# MCU_GPS_Comms.net
KiCad netlist of a schematic drawn in Altium Designer
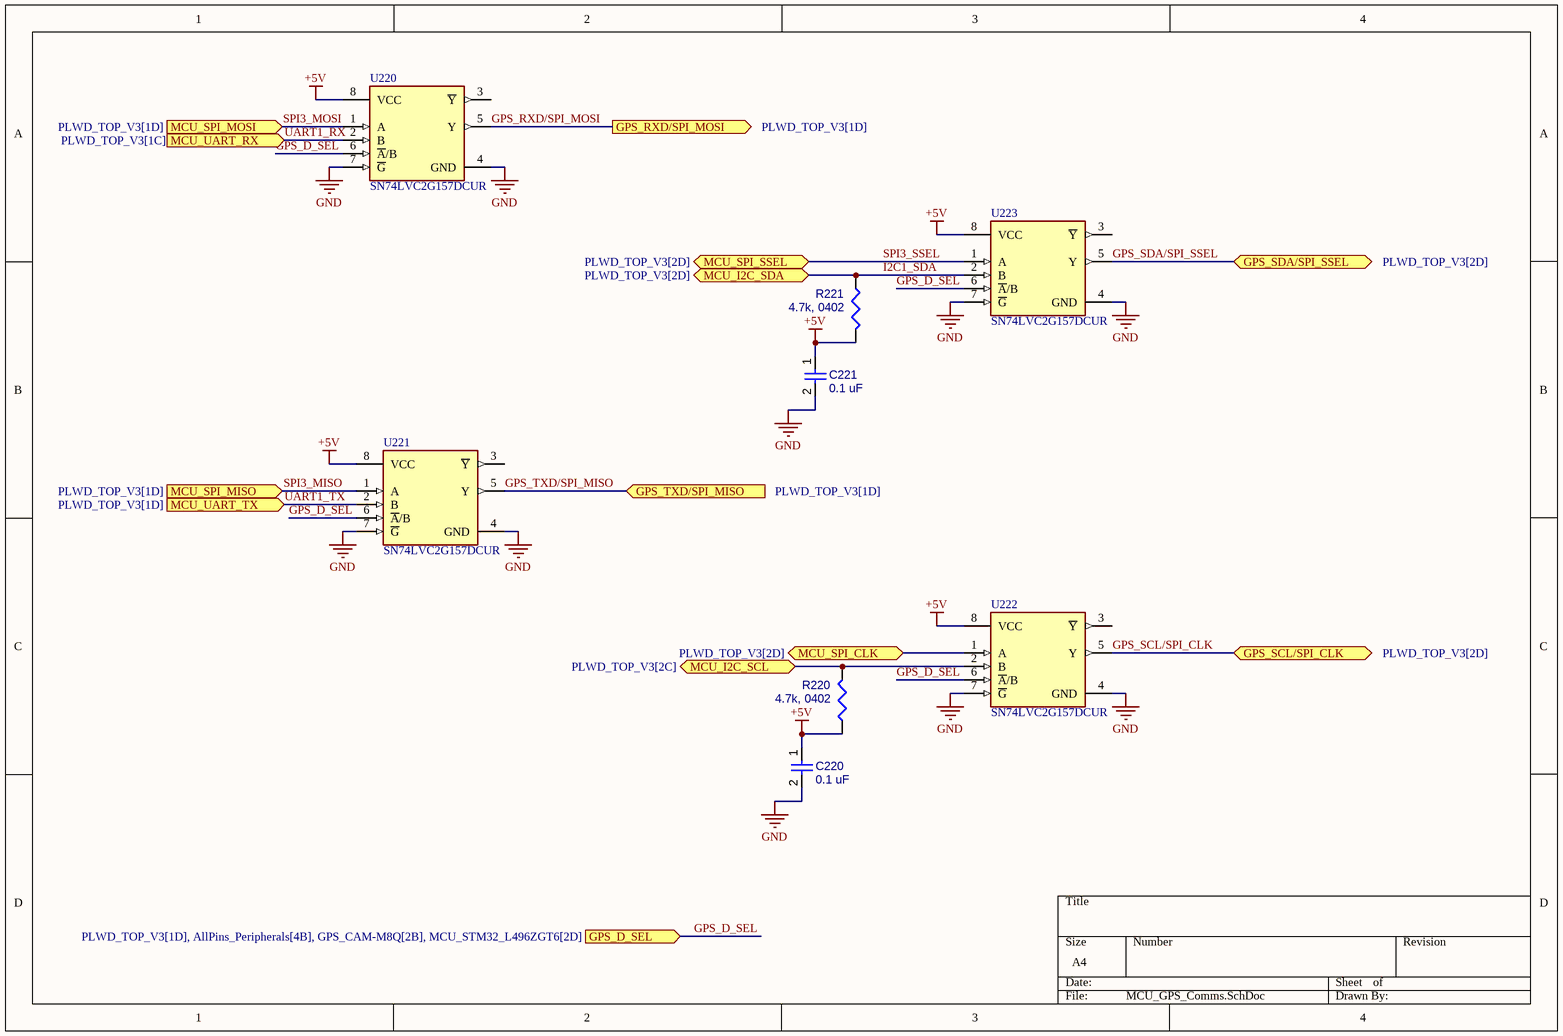
[diagram p0: MCU_GPS_Comms.SchDoc]

(export (version "E")
  (design (tool "Eeschema 10.0.6"))
  (components
    (comp (ref "C220")
      (value "0.1 uF")
      (footprint "CAPC1005X56X25LL10T15")
      (description "Chip Capacitor, 0.1 uF, +/- 5%, 16 V, 0402 (1005 Metric)")
      (fields (field (name "TOLERANCE") "5%"))
      (libsource (lib "Carleton University") (part "CAP-NP-2"))
    )
    (comp (ref "C221")
      (value "0.1 uF")
      (footprint "CAPC1005X56X25LL10T15")
      (description "Chip Capacitor, 0.1 uF, +/- 5%, 16 V, 0402 (1005 Metric)")
      (fields (field (name "TOLERANCE") "5%"))
      (libsource (lib "Carleton University") (part "CAP-NP-2"))
    )
    (comp (ref "R220")
      (value "4.7k, 0402")
      (footprint "RESC0402(1005)_L")
      (description "Chip Resistor, 4,7 kOhms, +/-1 %, 63 mW, -55 to 155 degC, 0402")
      (fields (field (name "POWER") "63mW") (field (name "TOLERANCE") "1%"))
      (libsource (lib "Carleton University") (part "RES-2"))
    )
    (comp (ref "R221")
      (value "4.7k, 0402")
      (footprint "RESC0402(1005)_L")
      (description "Chip Resistor, 4,7 kOhms, +/-1 %, 63 mW, -55 to 155 degC, 0402")
      (fields (field (name "POWER") "63mW") (field (name "TOLERANCE") "1%"))
      (libsource (lib "Carleton University") (part "RES-2"))
    )
    (comp (ref "U220")
      (value "SN74LVC2G157DCUR")
      (footprint "FP-DCU0008A-MFG")
      (description "IC MULTIPLEXER DATA SEL US8")
      (fields
        (field (name "MANUFACTURER") "Texas Instruments")
        (field (name "OCTOPART") "https://octopart.com/sn74lvc2g157dcur-texas+instruments-472190")
      )
      (libsource (lib "Altium Content Vault") (part "95628a67ef527f9f59f8dd49d4d18ae"))
    )
    (comp (ref "U221")
      (value "SN74LVC2G157DCUR")
      (footprint "FP-DCU0008A-MFG")
      (description "IC MULTIPLEXER DATA SEL US8")
      (fields
        (field (name "MANUFACTURER") "Texas Instruments")
        (field (name "OCTOPART") "https://octopart.com/sn74lvc2g157dcur-texas+instruments-472190")
      )
      (libsource (lib "Altium Content Vault") (part "95628a67ef527f9f59f8dd49d4d18ae"))
    )
    (comp (ref "U222")
      (value "SN74LVC2G157DCUR")
      (footprint "FP-DCU0008A-MFG")
      (description "IC MULTIPLEXER DATA SEL US8")
      (fields
        (field (name "MANUFACTURER") "Texas Instruments")
        (field (name "OCTOPART") "https://octopart.com/sn74lvc2g157dcur-texas+instruments-472190")
      )
      (libsource (lib "Altium Content Vault") (part "95628a67ef527f9f59f8dd49d4d18ae"))
    )
    (comp (ref "U223")
      (value "SN74LVC2G157DCUR")
      (footprint "FP-DCU0008A-MFG")
      (description "IC MULTIPLEXER DATA SEL US8")
      (fields
        (field (name "MANUFACTURER") "Texas Instruments")
        (field (name "OCTOPART") "https://octopart.com/sn74lvc2g157dcur-texas+instruments-472190")
      )
      (libsource (lib "Altium Content Vault") (part "95628a67ef527f9f59f8dd49d4d18ae"))
    )
  )
  (nets
    (net (code "1") (name "+5V") (class "Default")
      (node (ref "C220") (pin "1") (pinfunction "1_1") (pintype "passive"))
      (node (ref "C221") (pin "1") (pinfunction "1_1") (pintype "passive"))
      (node (ref "R220") (pin "1") (pinfunction "1_1") (pintype "passive"))
      (node (ref "R221") (pin "2") (pinfunction "2_2") (pintype "passive"))
      (node (ref "U220") (pin "8") (pinfunction "VCC_8") (pintype "power_in"))
      (node (ref "U221") (pin "8") (pinfunction "VCC_8") (pintype "power_in"))
      (node (ref "U222") (pin "8") (pinfunction "VCC_8") (pintype "power_in"))
      (node (ref "U223") (pin "8") (pinfunction "VCC_8") (pintype "power_in"))
    )
    (net (code "2") (name "/GPS_D_SEL") (class "Default")
      (node (ref "U220") (pin "6") (pinfunction "~{A}/B_6") (pintype "input"))
      (node (ref "U221") (pin "6") (pinfunction "~{A}/B_6") (pintype "input"))
      (node (ref "U222") (pin "6") (pinfunction "~{A}/B_6") (pintype "input"))
      (node (ref "U223") (pin "6") (pinfunction "~{A}/B_6") (pintype "input"))
    )
    (net (code "3") (name "/GPS_RXD{slash}SPI_MOSI") (class "Default")
      (node (ref "U220") (pin "5") (pinfunction "Y_5") (pintype "output"))
    )
    (net (code "4") (name "/GPS_SCL{slash}SPI_CLK") (class "Default")
      (node (ref "U222") (pin "5") (pinfunction "Y_5") (pintype "output"))
    )
    (net (code "5") (name "/GPS_SDA{slash}SPI_SSEL") (class "Default")
      (node (ref "U223") (pin "5") (pinfunction "Y_5") (pintype "output"))
    )
    (net (code "6") (name "/GPS_TXD{slash}SPI_MISO") (class "Default")
      (node (ref "U221") (pin "5") (pinfunction "Y_5") (pintype "output"))
    )
    (net (code "7") (name "/I2C1_SDA") (class "Default")
      (node (ref "R221") (pin "1") (pinfunction "1_1") (pintype "passive"))
      (node (ref "U223") (pin "2") (pinfunction "B_2") (pintype "input"))
    )
    (net (code "8") (name "/MCU_I2C_SCL") (class "Default")
      (node (ref "R220") (pin "2") (pinfunction "2_2") (pintype "passive"))
      (node (ref "U222") (pin "2") (pinfunction "B_2") (pintype "input"))
    )
    (net (code "9") (name "/MCU_SPI_CLK") (class "Default")
      (node (ref "U222") (pin "1") (pinfunction "A_1") (pintype "input"))
    )
    (net (code "10") (name "/SPI3_MISO") (class "Default")
      (node (ref "U221") (pin "1") (pinfunction "A_1") (pintype "input"))
    )
    (net (code "11") (name "/SPI3_MOSI") (class "Default")
      (node (ref "U220") (pin "1") (pinfunction "A_1") (pintype "input"))
    )
    (net (code "12") (name "/SPI3_SSEL") (class "Default")
      (node (ref "U223") (pin "1") (pinfunction "A_1") (pintype "input"))
    )
    (net (code "13") (name "/UART1_RX") (class "Default")
      (node (ref "U220") (pin "2") (pinfunction "B_2") (pintype "input"))
    )
    (net (code "14") (name "/UART1_TX") (class "Default")
      (node (ref "U221") (pin "2") (pinfunction "B_2") (pintype "input"))
    )
    (net (code "15") (name "GND") (class "Default")
      (node (ref "C220") (pin "2") (pinfunction "2_2") (pintype "passive"))
      (node (ref "C221") (pin "2") (pinfunction "2_2") (pintype "passive"))
      (node (ref "U220") (pin "4") (pinfunction "GND_4") (pintype "power_in"))
      (node (ref "U220") (pin "7") (pinfunction "~{G}_7") (pintype "input"))
      (node (ref "U221") (pin "4") (pinfunction "GND_4") (pintype "power_in"))
      (node (ref "U221") (pin "7") (pinfunction "~{G}_7") (pintype "input"))
      (node (ref "U222") (pin "4") (pinfunction "GND_4") (pintype "power_in"))
      (node (ref "U222") (pin "7") (pinfunction "~{G}_7") (pintype "input"))
      (node (ref "U223") (pin "4") (pinfunction "GND_4") (pintype "power_in"))
      (node (ref "U223") (pin "7") (pinfunction "~{G}_7") (pintype "input"))
    )
    (net (code "16") (name "unconnected-(U220-~{Y}-Pad3)") (class "Default")
      (node (ref "U220") (pin "3") (pinfunction "~{Y}_3") (pintype "output"))
    )
    (net (code "17") (name "unconnected-(U221-~{Y}-Pad3)") (class "Default")
      (node (ref "U221") (pin "3") (pinfunction "~{Y}_3") (pintype "output"))
    )
    (net (code "18") (name "unconnected-(U222-~{Y}-Pad3)") (class "Default")
      (node (ref "U222") (pin "3") (pinfunction "~{Y}_3") (pintype "output"))
    )
    (net (code "19") (name "unconnected-(U223-~{Y}-Pad3)") (class "Default")
      (node (ref "U223") (pin "3") (pinfunction "~{Y}_3") (pintype "output"))
    )
  )
)
